# Car.net
KiCad netlist of a schematic drawn in Altium Designer
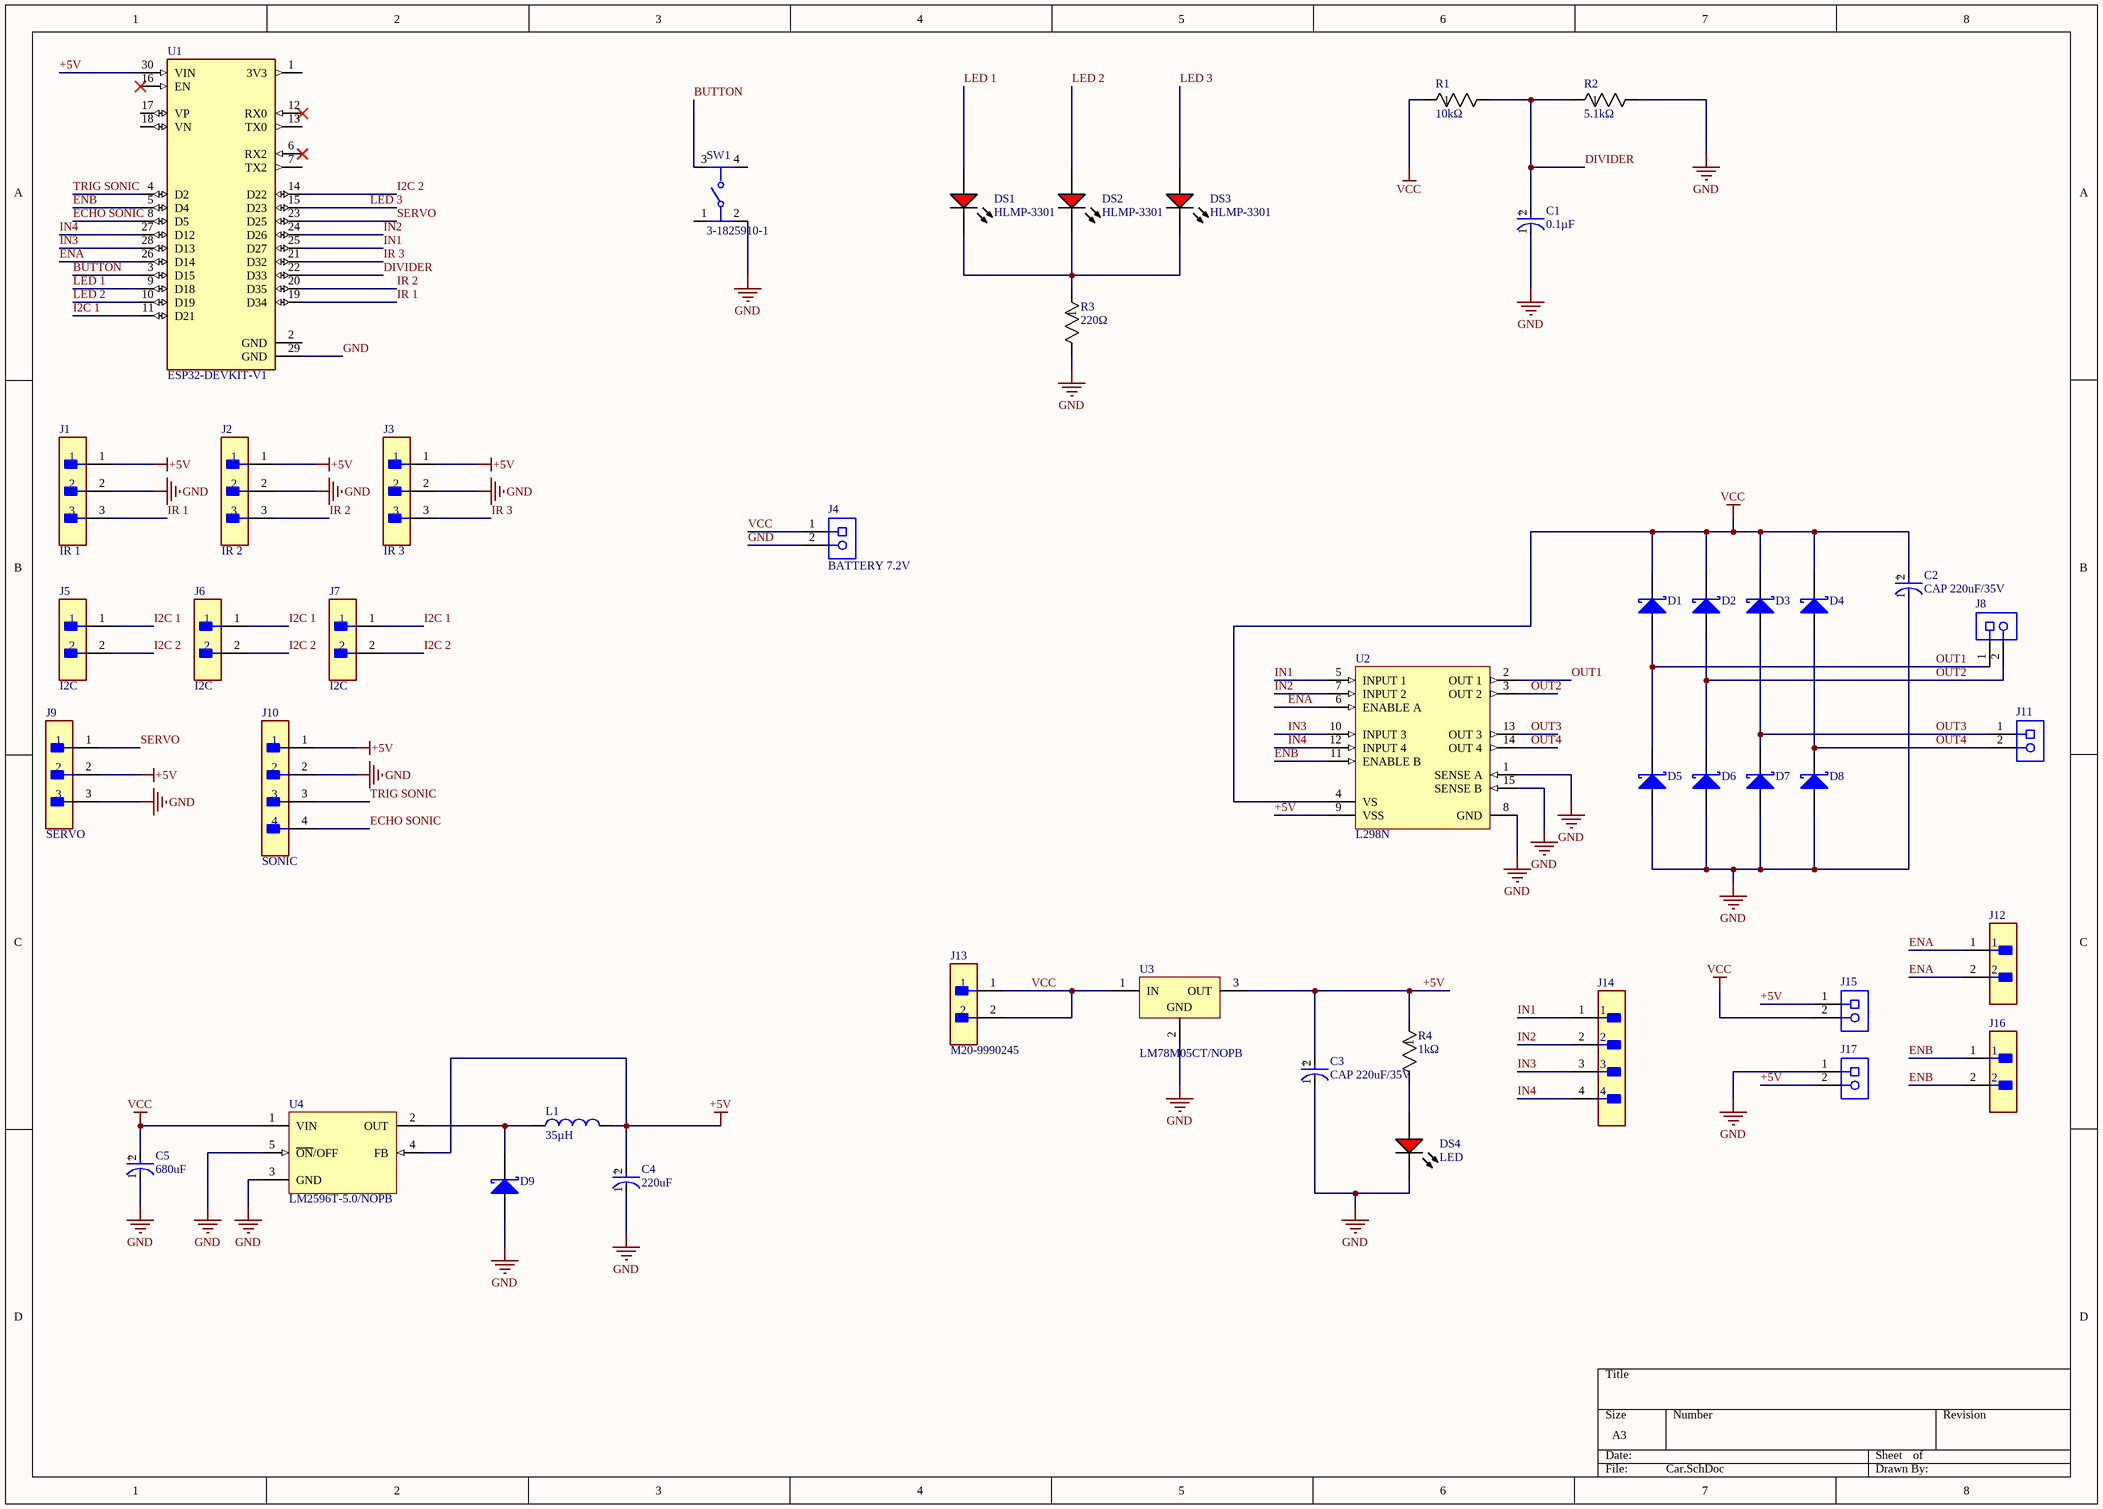
[diagram p0: Car.SchDoc]

(export (version "E")
  (design (tool "Eeschema 10.0.6"))
  (components
    (comp (ref "C1")
      (value "0.1µF")
      (footprint "FP-EEU-FR1H101B-MFG")
      (description "CAP ALUM 100UF 20% 50V RADIAL")
      (fields (field (name "TOLERANCE") "20%"))
      (libsource (lib "Altium Content Vault") (part "cf48714ba7e38822c1575c7ec0b6d1f"))
    )
    (comp (ref "C2")
      (value "CAP 220uF/35V")
      (footprint "FP-EEU-FR1H101B-MFG")
      (description "CAP ALUM 100UF 20% 50V RADIAL")
      (fields (field (name "TOLERANCE") "20%"))
      (libsource (lib "Altium Content Vault") (part "cf48714ba7e38822c1575c7ec0b6d1f"))
    )
    (comp (ref "C3")
      (value "CAP 220uF/35V")
      (footprint "FP-EEU-FR1H101B-MFG")
      (description "CAP ALUM 100UF 20% 50V RADIAL")
      (fields (field (name "TOLERANCE") "20%"))
      (libsource (lib "Altium Content Vault") (part "cf48714ba7e38822c1575c7ec0b6d1f"))
    )
    (comp (ref "C4")
      (value "220uF")
      (footprint "FP-EEU-FR1H101B-MFG")
      (description "CAP ALUM 100UF 20% 50V RADIAL")
      (fields (field (name "TOLERANCE") "20%"))
      (libsource (lib "Altium Content Vault") (part "cf48714ba7e38822c1575c7ec0b6d1f"))
    )
    (comp (ref "C5")
      (value "680uF")
      (footprint "FP-EEU-FR1H101B-MFG")
      (description "CAP ALUM 100UF 20% 50V RADIAL")
      (fields (field (name "TOLERANCE") "20%"))
      (libsource (lib "Altium Content Vault") (part "cf48714ba7e38822c1575c7ec0b6d1f"))
    )
    (comp (ref "D1")
      (value "BAT46")
      (footprint "STM-DO-35-2")
      (description "Small Signal Schottky Diode, 150 mA, 100 V, -65 to 125 degC, 2-Pin DO-35, RoHS, Tape and Reel")
      (fields (field (name "MANUFACTURER") "STMicroelectronics"))
      (libsource (lib "Altium Content Vault") (part "DSKY-AK-2"))
    )
    (comp (ref "D2")
      (value "BAT46")
      (footprint "STM-DO-35-2")
      (description "Small Signal Schottky Diode, 150 mA, 100 V, -65 to 125 degC, 2-Pin DO-35, RoHS, Tape and Reel")
      (fields (field (name "MANUFACTURER") "STMicroelectronics"))
      (libsource (lib "Altium Content Vault") (part "DSKY-AK-2"))
    )
    (comp (ref "D3")
      (value "BAT46")
      (footprint "STM-DO-35-2")
      (description "Small Signal Schottky Diode, 150 mA, 100 V, -65 to 125 degC, 2-Pin DO-35, RoHS, Tape and Reel")
      (fields (field (name "MANUFACTURER") "STMicroelectronics"))
      (libsource (lib "Altium Content Vault") (part "DSKY-AK-2"))
    )
    (comp (ref "D4")
      (value "BAT46")
      (footprint "STM-DO-35-2")
      (description "Small Signal Schottky Diode, 150 mA, 100 V, -65 to 125 degC, 2-Pin DO-35, RoHS, Tape and Reel")
      (fields (field (name "MANUFACTURER") "STMicroelectronics"))
      (libsource (lib "Altium Content Vault") (part "DSKY-AK-2"))
    )
    (comp (ref "D5")
      (value "BAT46")
      (footprint "STM-DO-35-2")
      (description "Small Signal Schottky Diode, 150 mA, 100 V, -65 to 125 degC, 2-Pin DO-35, RoHS, Tape and Reel")
      (fields (field (name "MANUFACTURER") "STMicroelectronics"))
      (libsource (lib "Altium Content Vault") (part "DSKY-AK-2"))
    )
    (comp (ref "D6")
      (value "BAT46")
      (footprint "STM-DO-35-2")
      (description "Small Signal Schottky Diode, 150 mA, 100 V, -65 to 125 degC, 2-Pin DO-35, RoHS, Tape and Reel")
      (fields (field (name "MANUFACTURER") "STMicroelectronics"))
      (libsource (lib "Altium Content Vault") (part "DSKY-AK-2"))
    )
    (comp (ref "D7")
      (value "BAT46")
      (footprint "STM-DO-35-2")
      (description "Small Signal Schottky Diode, 150 mA, 100 V, -65 to 125 degC, 2-Pin DO-35, RoHS, Tape and Reel")
      (fields (field (name "MANUFACTURER") "STMicroelectronics"))
      (libsource (lib "Altium Content Vault") (part "DSKY-AK-2"))
    )
    (comp (ref "D8")
      (value "BAT46")
      (footprint "STM-DO-35-2")
      (description "Small Signal Schottky Diode, 150 mA, 100 V, -65 to 125 degC, 2-Pin DO-35, RoHS, Tape and Reel")
      (fields (field (name "MANUFACTURER") "STMicroelectronics"))
      (libsource (lib "Altium Content Vault") (part "DSKY-AK-2"))
    )
    (comp (ref "D9")
      (value "BAT46")
      (footprint "STM-DO-35-2")
      (description "Small Signal Schottky Diode, 150 mA, 100 V, -65 to 125 degC, 2-Pin DO-35, RoHS, Tape and Reel")
      (fields (field (name "MANUFACTURER") "STMicroelectronics"))
      (libsource (lib "Altium Content Vault") (part "DSKY-AK-2"))
    )
    (comp (ref "DS1")
      (value "HLMP-3301")
      (footprint "AVAG-HLMP-3301-2")
      (description "T-1 3/4 (5 mm) Diffused LED Lamp, 1.9 V, -40 to 100 degC, 2-Pin THD, RoHS, Bulk")
      (fields (field (name "MANUFACTURER") "Avago"))
      (libsource (lib "Altium Content Vault") (part "LED-RED-K1A2-2"))
    )
    (comp (ref "DS2")
      (value "HLMP-3301")
      (footprint "AVAG-HLMP-3301-2")
      (description "T-1 3/4 (5 mm) Diffused LED Lamp, 1.9 V, -40 to 100 degC, 2-Pin THD, RoHS, Bulk")
      (fields (field (name "MANUFACTURER") "Avago"))
      (libsource (lib "Altium Content Vault") (part "LED-RED-K1A2-2"))
    )
    (comp (ref "DS3")
      (value "HLMP-3301")
      (footprint "AVAG-HLMP-3301-2")
      (description "T-1 3/4 (5 mm) Diffused LED Lamp, 1.9 V, -40 to 100 degC, 2-Pin THD, RoHS, Bulk")
      (fields (field (name "MANUFACTURER") "Avago"))
      (libsource (lib "Altium Content Vault") (part "LED-RED-K1A2-2"))
    )
    (comp (ref "DS4")
      (value "LED")
      (footprint "AVAG-HLMP-3301-2")
      (description "T-1 3/4 (5 mm) Diffused LED Lamp, 1.9 V, -40 to 100 degC, 2-Pin THD, RoHS, Bulk")
      (fields (field (name "MANUFACTURER") "Avago"))
      (libsource (lib "Altium Content Vault") (part "LED-RED-K1A2-2"))
    )
    (comp (ref "J1")
      (value "IR 1")
      (footprint "FP-B3B-XH-A_LF_SN-MFG")
      (description "CONN HEADER VERT 3POS 2.5MM")
      (libsource (lib "Altium Content Vault") (part "0d3f023dd272f625e17a2be33dea85f"))
    )
    (comp (ref "J2")
      (value "IR 2")
      (footprint "FP-B3B-XH-A_LF_SN-MFG")
      (description "CONN HEADER VERT 3POS 2.5MM")
      (libsource (lib "Altium Content Vault") (part "0d3f023dd272f625e17a2be33dea85f"))
    )
    (comp (ref "J3")
      (value "IR 3")
      (footprint "FP-B3B-XH-A_LF_SN-MFG")
      (description "CONN HEADER VERT 3POS 2.5MM")
      (libsource (lib "Altium Content Vault") (part "0d3f023dd272f625e17a2be33dea85f"))
    )
    (comp (ref "J4")
      (value "BATTERY 7.2V")
      (footprint "PHOE-1729128-2_V")
      (description "PCB Terminal Block, 13.5 A, 400 V, 2-Pin THD, RoHS, Bulk")
      (fields (field (name "PARTNUMBER") "1729128") (field (name "MANUFACTURER") "Phoenix Contact"))
      (libsource (lib "Altium Content Vault") (part "CN-2P-F-R2"))
    )
    (comp (ref "J5")
      (value "I2C")
      (footprint "FP-M20-9990245-MFG")
      (description "CONN HEADER VERT 2POS 2.54MM")
      (fields (field (name "VOLTAGE") "50V"))
      (libsource (lib "Altium Content Vault") (part "3bc925449376181038e59eaffc5286c"))
    )
    (comp (ref "J6")
      (value "I2C")
      (footprint "FP-M20-9990245-MFG")
      (description "CONN HEADER VERT 2POS 2.54MM")
      (fields (field (name "VOLTAGE") "50V"))
      (libsource (lib "Altium Content Vault") (part "3bc925449376181038e59eaffc5286c"))
    )
    (comp (ref "J7")
      (value "I2C")
      (footprint "FP-M20-9990245-MFG")
      (description "CONN HEADER VERT 2POS 2.54MM")
      (fields (field (name "VOLTAGE") "50V"))
      (libsource (lib "Altium Content Vault") (part "3bc925449376181038e59eaffc5286c"))
    )
    (comp (ref "J8")
      (value "1729128")
      (footprint "PHOE-1729128-2_V")
      (description "PCB Terminal Block, 13.5 A, 400 V, 2-Pin THD, RoHS, Bulk")
      (fields (field (name "MANUFACTURER") "Phoenix Contact"))
      (libsource (lib "") (part "CN-2P-F-R2_1"))
    )
    (comp (ref "J9")
      (value "SERVO")
      (footprint "FP-B3B-XH-A_LF_SN-MFG")
      (description "CONN HEADER VERT 3POS 2.5MM")
      (libsource (lib "Altium Content Vault") (part "0d3f023dd272f625e17a2be33dea85f"))
    )
    (comp (ref "J10")
      (value "SONIC")
      (footprint "FP-M20-9990445-MFG")
      (description "M20-9990445 Conn Unshrouded Header HDR 4 POS 2.54mm Solder ST Thru-Hole Bulk/Loose")
      (libsource (lib "") (part "299a8cea1bdcbc3624fe62c390fa72c_1"))
    )
    (comp (ref "J11")
      (value "1729128")
      (footprint "PHOE-1729128-2_V")
      (description "PCB Terminal Block, 13.5 A, 400 V, 2-Pin THD, RoHS, Bulk")
      (fields (field (name "MANUFACTURER") "Phoenix Contact"))
      (libsource (lib "Altium Content Vault") (part "CN-2P-F-R2"))
    )
    (comp (ref "J12")
      (value "M20-9990245")
      (footprint "FP-M20-9990245-MFG")
      (description "CONN HEADER VERT 2POS 2.54MM")
      (fields (field (name "VOLTAGE") "50V"))
      (libsource (lib "") (part "3bc925449376181038e59eaffc5286c_1"))
    )
    (comp (ref "J13")
      (value "M20-9990245")
      (footprint "FP-M20-9990245-MFG")
      (description "CONN HEADER VERT 2POS 2.54MM")
      (fields (field (name "VOLTAGE") "50V"))
      (libsource (lib "Altium Content Vault") (part "3bc925449376181038e59eaffc5286c"))
    )
    (comp (ref "J14")
      (value "M20-9990445")
      (footprint "FP-M20-9990445-MFG")
      (description "M20-9990445 Conn Unshrouded Header HDR 4 POS 2.54mm Solder ST Thru-Hole Bulk/Loose")
      (libsource (lib "Altium Content Vault") (part "299a8cea1bdcbc3624fe62c390fa72c"))
    )
    (comp (ref "J15")
      (value "1729128")
      (footprint "PHOE-1729128-2_V")
      (description "PCB Terminal Block, 13.5 A, 400 V, 2-Pin THD, RoHS, Bulk")
      (fields (field (name "MANUFACTURER") "Phoenix Contact"))
      (libsource (lib "Altium Content Vault") (part "CN-2P-F-R2"))
    )
    (comp (ref "J16")
      (value "M20-9990245")
      (footprint "FP-M20-9990245-MFG")
      (description "CONN HEADER VERT 2POS 2.54MM")
      (fields (field (name "VOLTAGE") "50V"))
      (libsource (lib "") (part "3bc925449376181038e59eaffc5286c_1"))
    )
    (comp (ref "J17")
      (value "1729128")
      (footprint "PHOE-1729128-2_V")
      (description "PCB Terminal Block, 13.5 A, 400 V, 2-Pin THD, RoHS, Bulk")
      (fields (field (name "MANUFACTURER") "Phoenix Contact"))
      (libsource (lib "Altium Content Vault") (part "CN-2P-F-R2"))
    )
    (comp (ref "L1")
      (value "35µH")
      (footprint "7447015")
      (description "7447015 35 µH ±20% Ferrite, Iron Powder Leaded Inductor, 5.7A Idc, 25mO Rdc WE-FI")
      (fields (field (name "TOLERANCE") "20%"))
      (libsource (lib "Altium Content Vault") (part "Inductor - 1"))
    )
    (comp (ref "R1")
      (value "10kΩ")
      (footprint "RES_AC03_VIS")
      (fields (field (name "TOLERANCE") "5%"))
      (libsource (lib "Altium Content Vault") (part "AC03000001000JAC00"))
    )
    (comp (ref "R2")
      (value "5.1kΩ")
      (footprint "RES_AC03_VIS")
      (fields (field (name "TOLERANCE") "5%"))
      (libsource (lib "Altium Content Vault") (part "AC03000001000JAC00"))
    )
    (comp (ref "R3")
      (value "220Ω")
      (footprint "RES_AC03_VIS")
      (fields (field (name "TOLERANCE") "5%"))
      (libsource (lib "Altium Content Vault") (part "AC03000001000JAC00"))
    )
    (comp (ref "R4")
      (value "1kΩ")
      (footprint "RES_AC03_VIS")
      (fields (field (name "TOLERANCE") "5%"))
      (libsource (lib "Altium Content Vault") (part "AC03000001000JAC00"))
    )
    (comp (ref "SW1")
      (value "3-1825910-1")
      (footprint "FP-3-1825910-1-MFG")
      (description "SWITCH TACTILE SPST-NO 0.05A 24V")
      (fields
        (field (name "MANUFACTURER") "TE Connectivity")
        (field (name "OCTOPART") "https://octopart.com/3-1825910-1-te+connectivity-46506874")
      )
      (libsource (lib "Altium Content Vault") (part "b8895f3f4cefb76e1819d2863dba89b"))
    )
    (comp (ref "U1")
      (value "ESP32-DEVKIT-V1")
      (footprint "MODULE_ESP32_DEVKIT_V1")
      (fields (field (name "MF") "Do it"))
      (libsource (lib "ESP32-DEVKIT-V1") (part "ESP32-DEVKIT-V1"))
    )
    (comp (ref "U2")
      (value "L298N")
      (footprint "STM-FM-15")
      (description "Dual Full-Bridge Driver, 4.8 to 46 V, -40 to 150 degC, 15-Pin FM (MW 15L), RoHS, Tube")
      (fields (field (name "MANUFACTURER") "STMicroelectronics") (field (name "PARTNUMBER") "L298"))
      (libsource (lib "Altium Content Vault") (part "STM-L298-15"))
    )
    (comp (ref "U3")
      (value "LM78M05CT/NOPB")
      (footprint "NDE0003A")
      (description "3-Terminal Positive Voltage Regulators, 3-pin TO-220, Pb-Free")
      (fields (field (name "MANUFACTURER") "Texas Instruments"))
      (libsource (lib "Altium Content Vault") (part "PM-REG-LM2940-SIL3"))
    )
    (comp (ref "U4")
      (value "LM2596T-5.0/NOPB")
      (footprint "NDH0005A")
      (description "SIMPLE SWITCHER® Power Converter 150 KHz 3A Step-Down Voltage Regulator, 5-pin TO-220, Pb-Free")
      (fields (field (name "MANUFACTURER") "Texas Instruments"))
      (libsource (lib "Altium Content Vault") (part "PM-REG-LM2575HVT-12"))
    )
  )
  (nets
    (net (code "1") (name "+5V") (class "Default")
      (node (ref "C3") (pin "2") (pinfunction "A_2") (pintype "passive"))
      (node (ref "C4") (pin "2") (pinfunction "A_2") (pintype "passive"))
      (node (ref "J1") (pin "1") (pinfunction "1_1") (pintype "passive"))
      (node (ref "J10") (pin "1") (pinfunction "1_1") (pintype "passive"))
      (node (ref "J15") (pin "1") (pinfunction "1_1") (pintype "passive"))
      (node (ref "J17") (pin "2") (pinfunction "2_2") (pintype "passive"))
      (node (ref "J2") (pin "1") (pinfunction "1_1") (pintype "passive"))
      (node (ref "J3") (pin "1") (pinfunction "1_1") (pintype "passive"))
      (node (ref "J9") (pin "2") (pinfunction "2_2") (pintype "passive"))
      (node (ref "L1") (pin "2") (pinfunction "2_2") (pintype "passive"))
      (node (ref "R4") (pin "1") (pinfunction "1_1") (pintype "passive"))
      (node (ref "U1") (pin "30") (pinfunction "VIN_30") (pintype "input"))
      (node (ref "U2") (pin "9") (pinfunction "VSS_9") (pintype "power_in"))
      (node (ref "U3") (pin "3") (pinfunction "OUT_3") (pintype "power_in"))
      (node (ref "U4") (pin "4") (pinfunction "FB_4") (pintype "input"))
    )
    (net (code "2") (name "/BUTTON") (class "Default")
      (node (ref "SW1") (pin "3") (pinfunction "3_3") (pintype "passive"))
      (node (ref "U1") (pin "3") (pinfunction "D15_3") (pintype "bidirectional"))
    )
    (net (code "3") (name "/DIVIDER") (class "Default")
      (node (ref "C1") (pin "2") (pinfunction "A_2") (pintype "passive"))
      (node (ref "R1") (pin "2") (pinfunction "2_2") (pintype "passive"))
      (node (ref "R2") (pin "1") (pinfunction "1_1") (pintype "passive"))
      (node (ref "U1") (pin "22") (pinfunction "D33_22") (pintype "bidirectional"))
    )
    (net (code "4") (name "/ECHO SONIC") (class "Default")
      (node (ref "J10") (pin "4") (pinfunction "4_4") (pintype "passive"))
      (node (ref "U1") (pin "8") (pinfunction "D5_8") (pintype "bidirectional"))
    )
    (net (code "5") (name "/ENA") (class "Default")
      (node (ref "J12") (pin "1") (pinfunction "1_1") (pintype "passive"))
      (node (ref "J12") (pin "2") (pinfunction "2_2") (pintype "passive"))
      (node (ref "U1") (pin "26") (pinfunction "D14_26") (pintype "bidirectional"))
      (node (ref "U2") (pin "6") (pinfunction "ENABLE_A_6") (pintype "input"))
    )
    (net (code "6") (name "/ENB") (class "Default")
      (node (ref "J16") (pin "1") (pinfunction "1_1") (pintype "passive"))
      (node (ref "J16") (pin "2") (pinfunction "2_2") (pintype "passive"))
      (node (ref "U1") (pin "5") (pinfunction "D4_5") (pintype "bidirectional"))
      (node (ref "U2") (pin "11") (pinfunction "ENABLE_B_11") (pintype "input"))
    )
    (net (code "7") (name "/I2C 1") (class "Default")
      (node (ref "J5") (pin "1") (pinfunction "1_1") (pintype "passive"))
      (node (ref "J6") (pin "1") (pinfunction "1_1") (pintype "passive"))
      (node (ref "J7") (pin "1") (pinfunction "1_1") (pintype "passive"))
      (node (ref "U1") (pin "11") (pinfunction "D21_11") (pintype "bidirectional"))
    )
    (net (code "8") (name "/I2C 2") (class "Default")
      (node (ref "J5") (pin "2") (pinfunction "2_2") (pintype "passive"))
      (node (ref "J6") (pin "2") (pinfunction "2_2") (pintype "passive"))
      (node (ref "J7") (pin "2") (pinfunction "2_2") (pintype "passive"))
      (node (ref "U1") (pin "14") (pinfunction "D22_14") (pintype "bidirectional"))
    )
    (net (code "9") (name "/IN1") (class "Default")
      (node (ref "J14") (pin "1") (pinfunction "1_1") (pintype "passive"))
      (node (ref "U1") (pin "25") (pinfunction "D27_25") (pintype "bidirectional"))
      (node (ref "U2") (pin "5") (pinfunction "INPUT_1_5") (pintype "input"))
    )
    (net (code "10") (name "/IN2") (class "Default")
      (node (ref "J14") (pin "2") (pinfunction "2_2") (pintype "passive"))
      (node (ref "U1") (pin "24") (pinfunction "D26_24") (pintype "bidirectional"))
      (node (ref "U2") (pin "7") (pinfunction "INPUT_2_7") (pintype "input"))
    )
    (net (code "11") (name "/IN3") (class "Default")
      (node (ref "J14") (pin "3") (pinfunction "3_3") (pintype "passive"))
      (node (ref "U1") (pin "28") (pinfunction "D13_28") (pintype "bidirectional"))
      (node (ref "U2") (pin "10") (pinfunction "INPUT_3_10") (pintype "input"))
    )
    (net (code "12") (name "/IN4") (class "Default")
      (node (ref "J14") (pin "4") (pinfunction "4_4") (pintype "passive"))
      (node (ref "U1") (pin "27") (pinfunction "D12_27") (pintype "bidirectional"))
      (node (ref "U2") (pin "12") (pinfunction "INPUT_4_12") (pintype "input"))
    )
    (net (code "13") (name "/IR 1") (class "Default")
      (node (ref "J1") (pin "3") (pinfunction "3_3") (pintype "passive"))
      (node (ref "U1") (pin "19") (pinfunction "D34_19") (pintype "bidirectional"))
    )
    (net (code "14") (name "/IR 2") (class "Default")
      (node (ref "J2") (pin "3") (pinfunction "3_3") (pintype "passive"))
      (node (ref "U1") (pin "20") (pinfunction "D35_20") (pintype "bidirectional"))
    )
    (net (code "15") (name "/IR 3") (class "Default")
      (node (ref "J3") (pin "3") (pinfunction "3_3") (pintype "passive"))
      (node (ref "U1") (pin "21") (pinfunction "D32_21") (pintype "bidirectional"))
    )
    (net (code "16") (name "/LED 1") (class "Default")
      (node (ref "DS1") (pin "2") (pinfunction "A_2") (pintype "passive"))
      (node (ref "U1") (pin "9") (pinfunction "D18_9") (pintype "bidirectional"))
    )
    (net (code "17") (name "/LED 2") (class "Default")
      (node (ref "DS2") (pin "2") (pinfunction "A_2") (pintype "passive"))
      (node (ref "U1") (pin "10") (pinfunction "D19_10") (pintype "bidirectional"))
    )
    (net (code "18") (name "/LED 3") (class "Default")
      (node (ref "DS3") (pin "2") (pinfunction "A_2") (pintype "passive"))
      (node (ref "U1") (pin "15") (pinfunction "D23_15") (pintype "bidirectional"))
    )
    (net (code "19") (name "/OUT1") (class "Default")
      (node (ref "D1") (pin "1") (pinfunction "A_1") (pintype "passive"))
      (node (ref "D5") (pin "2") (pinfunction "K_2") (pintype "passive"))
      (node (ref "J8") (pin "1") (pinfunction "1_1") (pintype "passive"))
      (node (ref "U2") (pin "2") (pinfunction "OUT_1_2") (pintype "output"))
    )
    (net (code "20") (name "/OUT2") (class "Default")
      (node (ref "D2") (pin "1") (pinfunction "A_1") (pintype "passive"))
      (node (ref "D6") (pin "2") (pinfunction "K_2") (pintype "passive"))
      (node (ref "J8") (pin "2") (pinfunction "2_2") (pintype "passive"))
      (node (ref "U2") (pin "3") (pinfunction "OUT_2_3") (pintype "output"))
    )
    (net (code "21") (name "/OUT3") (class "Default")
      (node (ref "D3") (pin "1") (pinfunction "A_1") (pintype "passive"))
      (node (ref "D7") (pin "2") (pinfunction "K_2") (pintype "passive"))
      (node (ref "J11") (pin "1") (pinfunction "1_1") (pintype "passive"))
      (node (ref "U2") (pin "13") (pinfunction "OUT_3_13") (pintype "output"))
    )
    (net (code "22") (name "/OUT4") (class "Default")
      (node (ref "D4") (pin "1") (pinfunction "A_1") (pintype "passive"))
      (node (ref "D8") (pin "2") (pinfunction "K_2") (pintype "passive"))
      (node (ref "J11") (pin "2") (pinfunction "2_2") (pintype "passive"))
      (node (ref "U2") (pin "14") (pinfunction "OUT_4_14") (pintype "output"))
    )
    (net (code "23") (name "/SERVO") (class "Default")
      (node (ref "J9") (pin "1") (pinfunction "1_1") (pintype "passive"))
      (node (ref "U1") (pin "23") (pinfunction "D25_23") (pintype "bidirectional"))
    )
    (net (code "24") (name "/TRIG SONIC") (class "Default")
      (node (ref "J10") (pin "3") (pinfunction "3_3") (pintype "passive"))
      (node (ref "U1") (pin "4") (pinfunction "D2_4") (pintype "bidirectional"))
    )
    (net (code "25") (name "GND") (class "Default")
      (node (ref "C1") (pin "1") (pinfunction "C_1") (pintype "passive"))
      (node (ref "C2") (pin "1") (pinfunction "C_1") (pintype "passive"))
      (node (ref "C3") (pin "1") (pinfunction "C_1") (pintype "passive"))
      (node (ref "C4") (pin "1") (pinfunction "C_1") (pintype "passive"))
      (node (ref "C5") (pin "1") (pinfunction "C_1") (pintype "passive"))
      (node (ref "D5") (pin "1") (pinfunction "A_1") (pintype "passive"))
      (node (ref "D6") (pin "1") (pinfunction "A_1") (pintype "passive"))
      (node (ref "D7") (pin "1") (pinfunction "A_1") (pintype "passive"))
      (node (ref "D8") (pin "1") (pinfunction "A_1") (pintype "passive"))
      (node (ref "D9") (pin "1") (pinfunction "A_1") (pintype "passive"))
      (node (ref "DS4") (pin "1") (pinfunction "K_1") (pintype "passive"))
      (node (ref "J1") (pin "2") (pinfunction "2_2") (pintype "passive"))
      (node (ref "J10") (pin "2") (pinfunction "2_2") (pintype "passive"))
      (node (ref "J17") (pin "1") (pinfunction "1_1") (pintype "passive"))
      (node (ref "J2") (pin "2") (pinfunction "2_2") (pintype "passive"))
      (node (ref "J3") (pin "2") (pinfunction "2_2") (pintype "passive"))
      (node (ref "J4") (pin "2") (pinfunction "2_2") (pintype "passive"))
      (node (ref "J9") (pin "3") (pinfunction "3_3") (pintype "passive"))
      (node (ref "R2") (pin "2") (pinfunction "2_2") (pintype "passive"))
      (node (ref "R3") (pin "2") (pinfunction "2_2") (pintype "passive"))
      (node (ref "SW1") (pin "2") (pinfunction "2_2") (pintype "passive"))
      (node (ref "U1") (pin "29") (pinfunction "GND_29") (pintype "power_in"))
      (node (ref "U2") (pin "1") (pinfunction "SENSE_A_1") (pintype "input"))
      (node (ref "U2") (pin "15") (pinfunction "SENSE_B_15") (pintype "input"))
      (node (ref "U2") (pin "8") (pinfunction "GND_8") (pintype "power_in"))
      (node (ref "U3") (pin "2") (pinfunction "GND_2") (pintype "power_in"))
      (node (ref "U4") (pin "3") (pinfunction "GND_3") (pintype "power_in"))
      (node (ref "U4") (pin "5") (pinfunction "~{ON}/OFF_5") (pintype "input"))
    )
    (net (code "26") (name "Net-(D9-K)") (class "Default")
      (node (ref "D9") (pin "2") (pinfunction "K_2") (pintype "passive"))
      (node (ref "L1") (pin "1") (pinfunction "1_1") (pintype "passive"))
      (node (ref "U4") (pin "2") (pinfunction "OUT_2") (pintype "power_in"))
    )
    (net (code "27") (name "Net-(DS1-K)") (class "Default")
      (node (ref "DS1") (pin "1") (pinfunction "K_1") (pintype "passive"))
      (node (ref "DS2") (pin "1") (pinfunction "K_1") (pintype "passive"))
      (node (ref "DS3") (pin "1") (pinfunction "K_1") (pintype "passive"))
      (node (ref "R3") (pin "1") (pinfunction "1_1") (pintype "passive"))
    )
    (net (code "28") (name "Net-(DS4-A)") (class "Default")
      (node (ref "DS4") (pin "2") (pinfunction "A_2") (pintype "passive"))
      (node (ref "R4") (pin "2") (pinfunction "2_2") (pintype "passive"))
    )
    (net (code "29") (name "VCC") (class "Default")
      (node (ref "C2") (pin "2") (pinfunction "A_2") (pintype "passive"))
      (node (ref "C5") (pin "2") (pinfunction "A_2") (pintype "passive"))
      (node (ref "D1") (pin "2") (pinfunction "K_2") (pintype "passive"))
      (node (ref "D2") (pin "2") (pinfunction "K_2") (pintype "passive"))
      (node (ref "D3") (pin "2") (pinfunction "K_2") (pintype "passive"))
      (node (ref "D4") (pin "2") (pinfunction "K_2") (pintype "passive"))
      (node (ref "J13") (pin "1") (pinfunction "1_1") (pintype "passive"))
      (node (ref "J13") (pin "2") (pinfunction "2_2") (pintype "passive"))
      (node (ref "J15") (pin "2") (pinfunction "2_2") (pintype "passive"))
      (node (ref "J4") (pin "1") (pinfunction "1_1") (pintype "passive"))
      (node (ref "R1") (pin "1") (pinfunction "1_1") (pintype "passive"))
      (node (ref "U2") (pin "4") (pinfunction "VS_4") (pintype "power_in"))
      (node (ref "U3") (pin "1") (pinfunction "IN_1") (pintype "power_in"))
      (node (ref "U4") (pin "1") (pinfunction "VIN_1") (pintype "power_in"))
    )
    (net (code "30") (name "unconnected-(SW1-Pad1)") (class "Default")
      (node (ref "SW1") (pin "1") (pinfunction "1_1") (pintype "passive"))
    )
    (net (code "31") (name "unconnected-(SW1-Pad4)") (class "Default")
      (node (ref "SW1") (pin "4") (pinfunction "4_4") (pintype "passive"))
    )
    (net (code "32") (name "unconnected-(U1-3V3-Pad1)") (class "Default")
      (node (ref "U1") (pin "1") (pinfunction "3V3_1") (pintype "output"))
    )
    (net (code "33") (name "unconnected-(U1-EN-Pad16)") (class "Default")
      (node (ref "U1") (pin "16") (pinfunction "EN_16") (pintype "input+no_connect"))
    )
    (net (code "34") (name "unconnected-(U1-GND-Pad2)") (class "Default")
      (node (ref "U1") (pin "2") (pinfunction "GND_2") (pintype "power_in"))
    )
    (net (code "35") (name "unconnected-(U1-RX0-Pad12)") (class "Default")
      (node (ref "U1") (pin "12") (pinfunction "RX0_12") (pintype "input+no_connect"))
    )
    (net (code "36") (name "unconnected-(U1-RX2-Pad6)") (class "Default")
      (node (ref "U1") (pin "6") (pinfunction "RX2_6") (pintype "input+no_connect"))
    )
    (net (code "37") (name "unconnected-(U1-TX0-Pad13)") (class "Default")
      (node (ref "U1") (pin "13") (pinfunction "TX0_13") (pintype "output"))
    )
    (net (code "38") (name "unconnected-(U1-TX2-Pad7)") (class "Default")
      (node (ref "U1") (pin "7") (pinfunction "TX2_7") (pintype "output"))
    )
    (net (code "39") (name "unconnected-(U1-VN-Pad18)") (class "Default")
      (node (ref "U1") (pin "18") (pinfunction "VN_18") (pintype "bidirectional"))
    )
    (net (code "40") (name "unconnected-(U1-VP-Pad17)") (class "Default")
      (node (ref "U1") (pin "17") (pinfunction "VP_17") (pintype "bidirectional"))
    )
  )
)
